# 4_serial_LSA.net
KiCad netlist of a schematic drawn in EAGLE
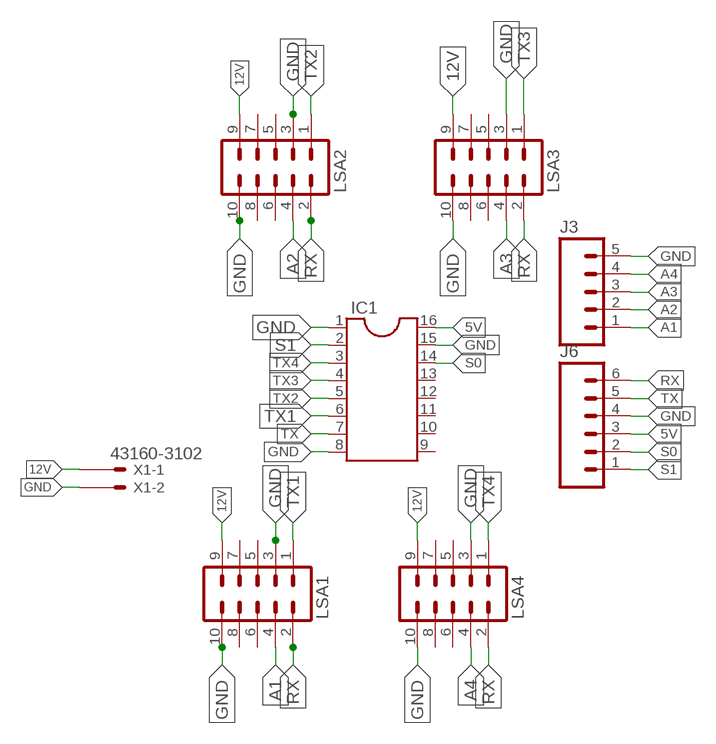
[diagram p0: schematic, sheet 1]

(export (version "E")
  (design (tool "Eeschema 10.0.6"))
  (components
    (comp (ref "IC1")
      (value "DIL16S")
      (footprint "eagle-import:SOCKET-16")
      (libsource (lib "eagle-import") (part "DIL16S"))
    )
    (comp (ref "J3")
      (value "M05PTH")
      (footprint "eagle-import:1X05")
      (fields (field (name "SPICEPREFIX") "X"))
      (libsource (lib "eagle-import") (part "M05PTH"))
    )
    (comp (ref "J6")
      (value "M06SILK_FEMALE_PTH")
      (footprint "eagle-import:1X06")
      (libsource (lib "eagle-import") (part "M06SILK_FEMALE_PTH"))
    )
    (comp (ref "LSA1")
      (value "M05X2SHD_LOCK")
      (footprint "eagle-import:2X5-SHROUDED_LOCK")
      (libsource (lib "eagle-import") (part "M05X2SHD_LOCK"))
    )
    (comp (ref "LSA2")
      (value "M05X2SHD_LOCK")
      (footprint "eagle-import:2X5-SHROUDED_LOCK")
      (libsource (lib "eagle-import") (part "M05X2SHD_LOCK"))
    )
    (comp (ref "LSA3")
      (value "M05X2SHD_LOCK")
      (footprint "eagle-import:2X5-SHROUDED_LOCK")
      (libsource (lib "eagle-import") (part "M05X2SHD_LOCK"))
    )
    (comp (ref "LSA4")
      (value "M05X2SHD_LOCK")
      (footprint "eagle-import:2X5-SHROUDED_LOCK")
      (libsource (lib "eagle-import") (part "M05X2SHD_LOCK"))
    )
    (comp (ref "X1")
      (value "43160-3102")
      (footprint "eagle-import:43160-XX02")
      (fields (field (name "MF") "WALDOM/MOLEX"))
      (libsource (lib "eagle-import") (part "43160-0231"))
    )
  )
  (nets
    (net (code "1") (name "5V") (class "Default")
      (node (ref "IC1") (pin "16") (pinfunction "16_16") (pintype "passive"))
      (node (ref "J6") (pin "3") (pinfunction "3_3") (pintype "passive"))
    )
    (net (code "2") (name "12V") (class "Default")
      (node (ref "LSA1") (pin "9") (pinfunction "9_9") (pintype "passive"))
      (node (ref "LSA2") (pin "9") (pinfunction "9_9") (pintype "passive"))
      (node (ref "LSA3") (pin "9") (pinfunction "9_9") (pintype "passive"))
      (node (ref "LSA4") (pin "9") (pinfunction "9_9") (pintype "passive"))
      (node (ref "X1") (pin "1@1") (pinfunction "S_1@1") (pintype "passive"))
    )
    (net (code "3") (name "A1") (class "Default")
      (node (ref "J3") (pin "1") (pinfunction "1_1") (pintype "passive"))
      (node (ref "LSA1") (pin "4") (pinfunction "4_4") (pintype "passive"))
    )
    (net (code "4") (name "A2") (class "Default")
      (node (ref "J3") (pin "2") (pinfunction "2_2") (pintype "passive"))
      (node (ref "LSA2") (pin "4") (pinfunction "4_4") (pintype "passive"))
    )
    (net (code "5") (name "A3") (class "Default")
      (node (ref "J3") (pin "3") (pinfunction "3_3") (pintype "passive"))
      (node (ref "LSA3") (pin "4") (pinfunction "4_4") (pintype "passive"))
    )
    (net (code "6") (name "A4") (class "Default")
      (node (ref "J3") (pin "4") (pinfunction "4_4") (pintype "passive"))
      (node (ref "LSA4") (pin "4") (pinfunction "4_4") (pintype "passive"))
    )
    (net (code "7") (name "GND") (class "Default")
      (node (ref "IC1") (pin "1") (pinfunction "1_1") (pintype "passive"))
      (node (ref "IC1") (pin "15") (pinfunction "15_15") (pintype "passive"))
      (node (ref "IC1") (pin "8") (pinfunction "8_8") (pintype "passive"))
      (node (ref "J3") (pin "5") (pinfunction "5_5") (pintype "passive"))
      (node (ref "J6") (pin "4") (pinfunction "4_4") (pintype "passive"))
      (node (ref "LSA1") (pin "10") (pinfunction "10_10") (pintype "passive"))
      (node (ref "LSA1") (pin "3") (pinfunction "3_3") (pintype "passive"))
      (node (ref "LSA2") (pin "10") (pinfunction "10_10") (pintype "passive"))
      (node (ref "LSA2") (pin "3") (pinfunction "3_3") (pintype "passive"))
      (node (ref "LSA3") (pin "10") (pinfunction "10_10") (pintype "passive"))
      (node (ref "LSA3") (pin "3") (pinfunction "3_3") (pintype "passive"))
      (node (ref "LSA4") (pin "10") (pinfunction "10_10") (pintype "passive"))
      (node (ref "LSA4") (pin "3") (pinfunction "3_3") (pintype "passive"))
      (node (ref "X1") (pin "2@1") (pinfunction "S_2@1") (pintype "passive"))
    )
    (net (code "8") (name "RX") (class "Default")
      (node (ref "J6") (pin "6") (pinfunction "6_6") (pintype "passive"))
      (node (ref "LSA1") (pin "2") (pinfunction "2_2") (pintype "passive"))
      (node (ref "LSA2") (pin "2") (pinfunction "2_2") (pintype "passive"))
      (node (ref "LSA3") (pin "2") (pinfunction "2_2") (pintype "passive"))
      (node (ref "LSA4") (pin "2") (pinfunction "2_2") (pintype "passive"))
    )
    (net (code "9") (name "S0") (class "Default")
      (node (ref "IC1") (pin "14") (pinfunction "14_14") (pintype "passive"))
      (node (ref "J6") (pin "2") (pinfunction "2_2") (pintype "passive"))
    )
    (net (code "10") (name "S1") (class "Default")
      (node (ref "IC1") (pin "2") (pinfunction "2_2") (pintype "passive"))
      (node (ref "J6") (pin "1") (pinfunction "1_1") (pintype "passive"))
    )
    (net (code "11") (name "TX") (class "Default")
      (node (ref "IC1") (pin "7") (pinfunction "7_7") (pintype "passive"))
      (node (ref "J6") (pin "5") (pinfunction "5_5") (pintype "passive"))
    )
    (net (code "12") (name "TX1") (class "Default")
      (node (ref "IC1") (pin "6") (pinfunction "6_6") (pintype "passive"))
      (node (ref "LSA1") (pin "1") (pinfunction "1_1") (pintype "passive"))
    )
    (net (code "13") (name "TX2") (class "Default")
      (node (ref "IC1") (pin "5") (pinfunction "5_5") (pintype "passive"))
      (node (ref "LSA2") (pin "1") (pinfunction "1_1") (pintype "passive"))
    )
    (net (code "14") (name "TX3") (class "Default")
      (node (ref "IC1") (pin "4") (pinfunction "4_4") (pintype "passive"))
      (node (ref "LSA3") (pin "1") (pinfunction "1_1") (pintype "passive"))
    )
    (net (code "15") (name "TX4") (class "Default")
      (node (ref "IC1") (pin "3") (pinfunction "3_3") (pintype "passive"))
      (node (ref "LSA4") (pin "1") (pinfunction "1_1") (pintype "passive"))
    )
    (net (code "16") (name "unconnected-(IC1-Pad9)") (class "Default")
      (node (ref "IC1") (pin "9") (pinfunction "9_9") (pintype "passive"))
    )
    (net (code "17") (name "unconnected-(IC1-Pad10)") (class "Default")
      (node (ref "IC1") (pin "10") (pinfunction "10_10") (pintype "passive"))
    )
    (net (code "18") (name "unconnected-(IC1-Pad11)") (class "Default")
      (node (ref "IC1") (pin "11") (pinfunction "11_11") (pintype "passive"))
    )
    (net (code "19") (name "unconnected-(IC1-Pad12)") (class "Default")
      (node (ref "IC1") (pin "12") (pinfunction "12_12") (pintype "passive"))
    )
    (net (code "20") (name "unconnected-(IC1-Pad13)") (class "Default")
      (node (ref "IC1") (pin "13") (pinfunction "13_13") (pintype "passive"))
    )
    (net (code "21") (name "unconnected-(LSA1-Pad5)") (class "Default")
      (node (ref "LSA1") (pin "5") (pinfunction "5_5") (pintype "passive"))
    )
    (net (code "22") (name "unconnected-(LSA1-Pad6)") (class "Default")
      (node (ref "LSA1") (pin "6") (pinfunction "6_6") (pintype "passive"))
    )
    (net (code "23") (name "unconnected-(LSA1-Pad7)") (class "Default")
      (node (ref "LSA1") (pin "7") (pinfunction "7_7") (pintype "passive"))
    )
    (net (code "24") (name "unconnected-(LSA1-Pad8)") (class "Default")
      (node (ref "LSA1") (pin "8") (pinfunction "8_8") (pintype "passive"))
    )
    (net (code "25") (name "unconnected-(LSA2-Pad5)") (class "Default")
      (node (ref "LSA2") (pin "5") (pinfunction "5_5") (pintype "passive"))
    )
    (net (code "26") (name "unconnected-(LSA2-Pad6)") (class "Default")
      (node (ref "LSA2") (pin "6") (pinfunction "6_6") (pintype "passive"))
    )
    (net (code "27") (name "unconnected-(LSA2-Pad7)") (class "Default")
      (node (ref "LSA2") (pin "7") (pinfunction "7_7") (pintype "passive"))
    )
    (net (code "28") (name "unconnected-(LSA2-Pad8)") (class "Default")
      (node (ref "LSA2") (pin "8") (pinfunction "8_8") (pintype "passive"))
    )
    (net (code "29") (name "unconnected-(LSA3-Pad5)") (class "Default")
      (node (ref "LSA3") (pin "5") (pinfunction "5_5") (pintype "passive"))
    )
    (net (code "30") (name "unconnected-(LSA3-Pad6)") (class "Default")
      (node (ref "LSA3") (pin "6") (pinfunction "6_6") (pintype "passive"))
    )
    (net (code "31") (name "unconnected-(LSA3-Pad7)") (class "Default")
      (node (ref "LSA3") (pin "7") (pinfunction "7_7") (pintype "passive"))
    )
    (net (code "32") (name "unconnected-(LSA3-Pad8)") (class "Default")
      (node (ref "LSA3") (pin "8") (pinfunction "8_8") (pintype "passive"))
    )
    (net (code "33") (name "unconnected-(LSA4-Pad5)") (class "Default")
      (node (ref "LSA4") (pin "5") (pinfunction "5_5") (pintype "passive"))
    )
    (net (code "34") (name "unconnected-(LSA4-Pad6)") (class "Default")
      (node (ref "LSA4") (pin "6") (pinfunction "6_6") (pintype "passive"))
    )
    (net (code "35") (name "unconnected-(LSA4-Pad7)") (class "Default")
      (node (ref "LSA4") (pin "7") (pinfunction "7_7") (pintype "passive"))
    )
    (net (code "36") (name "unconnected-(LSA4-Pad8)") (class "Default")
      (node (ref "LSA4") (pin "8") (pinfunction "8_8") (pintype "passive"))
    )
    (net (code "37") (name "unconnected-(X1A-S-Pad1@2)") (class "Default")
      (node (ref "X1") (pin "1@2") (pinfunction "S_1@2") (pintype "passive"))
    )
    (net (code "38") (name "unconnected-(X1B-S-Pad2@2)") (class "Default")
      (node (ref "X1") (pin "2@2") (pinfunction "S_2@2") (pintype "passive"))
    )
  )
)
